# Trainiiii_Cape.net
KiCad netlist of a schematic drawn in EAGLE
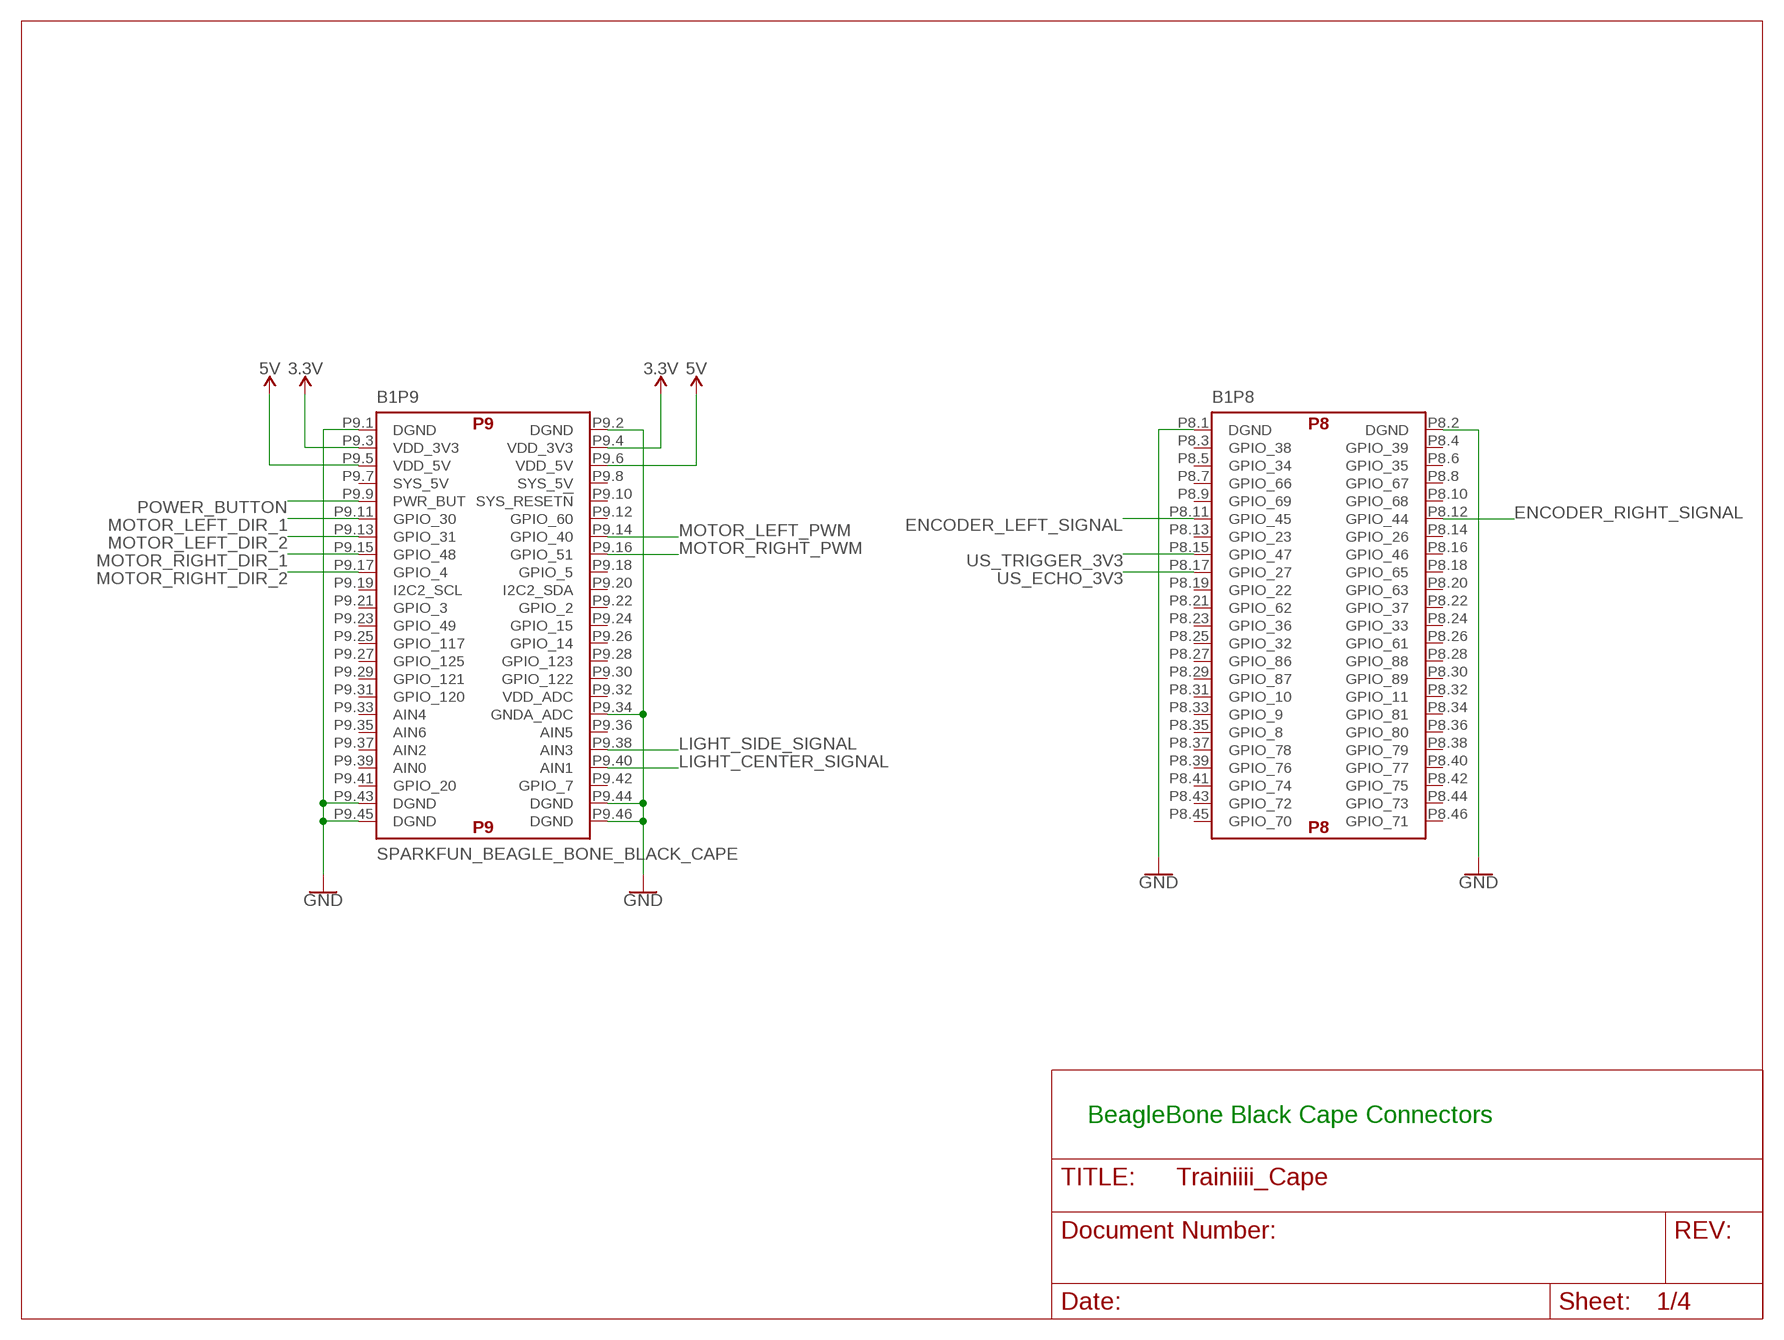
[diagram p0: schematic, sheet 1]
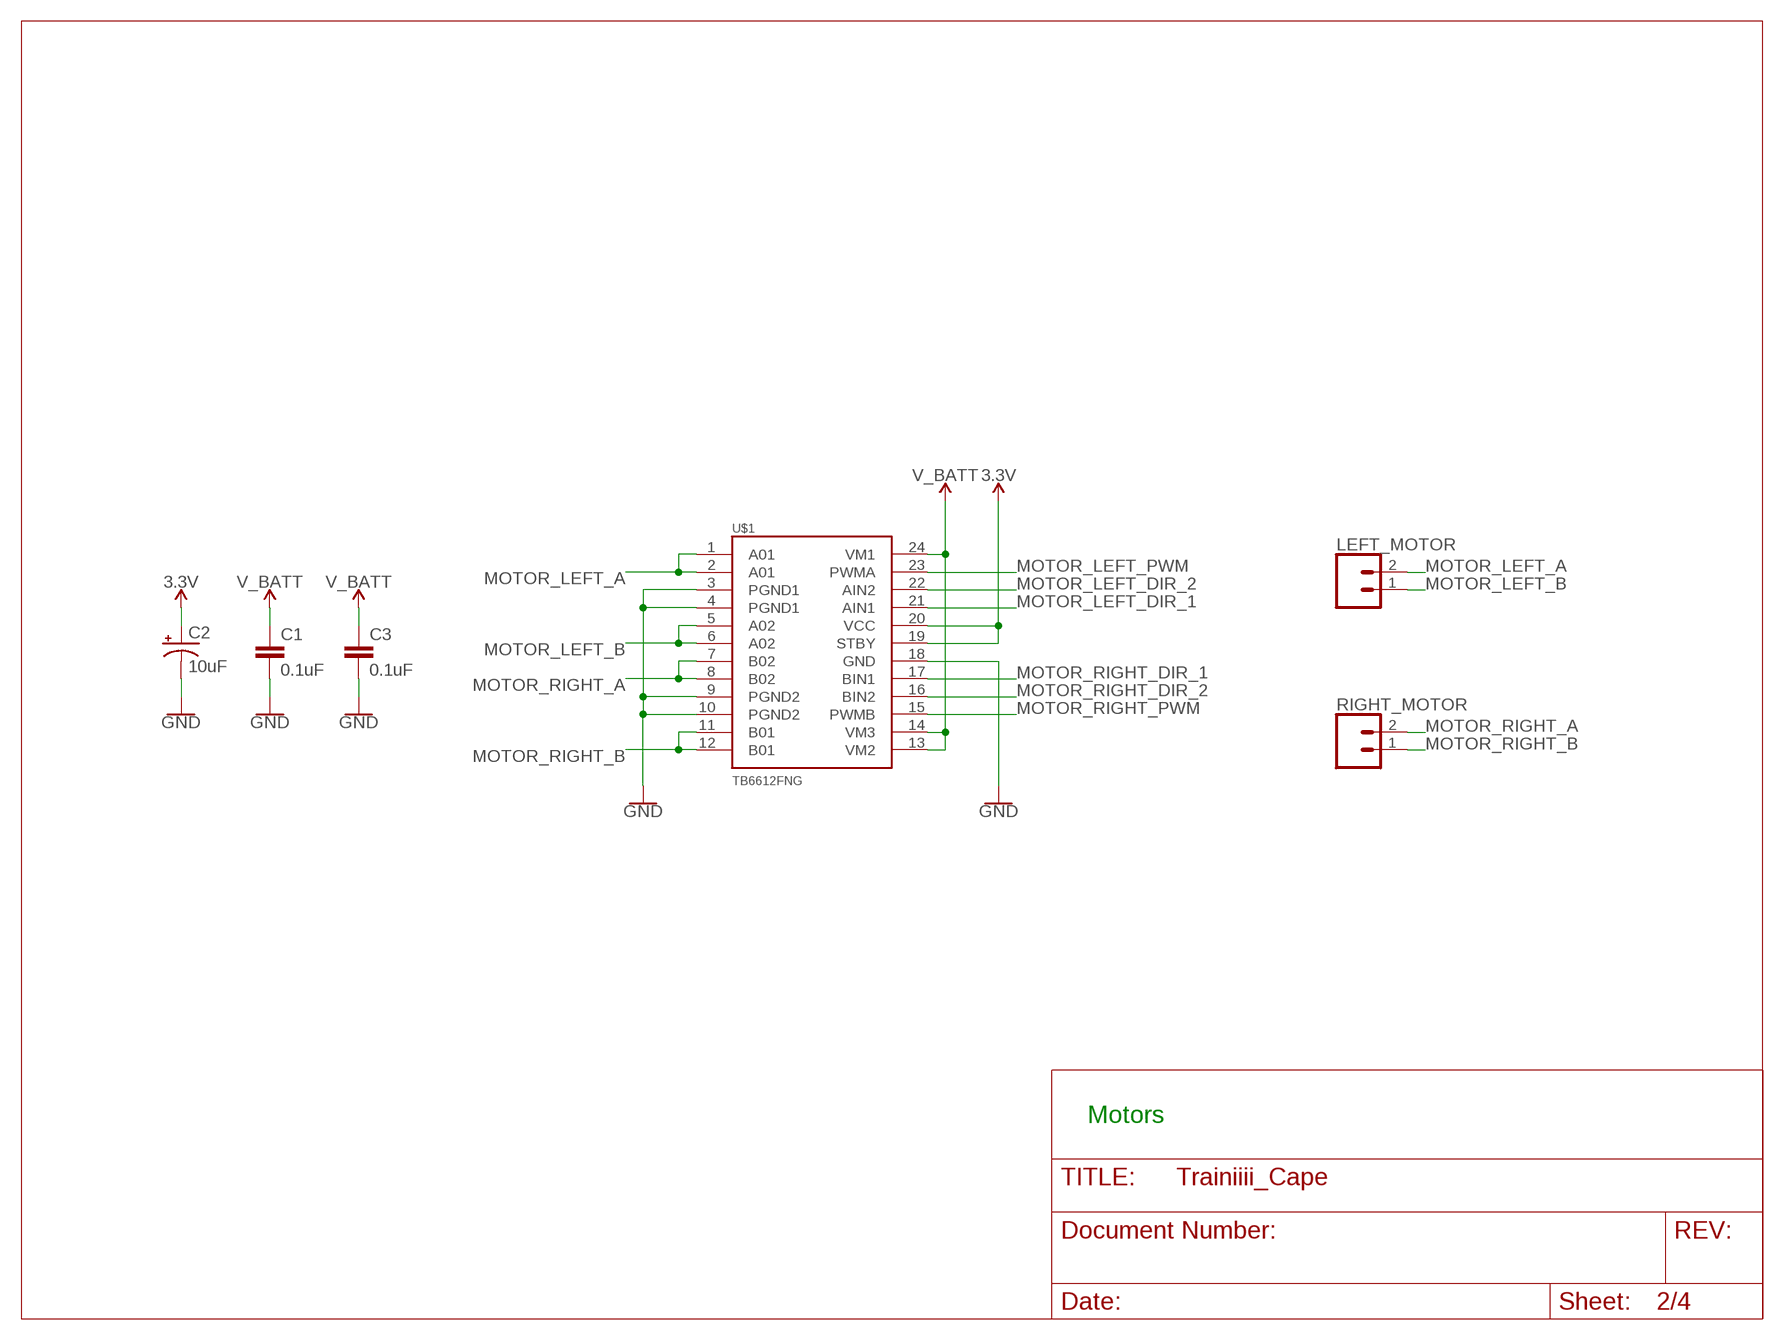
[diagram p1: schematic, sheet 2]
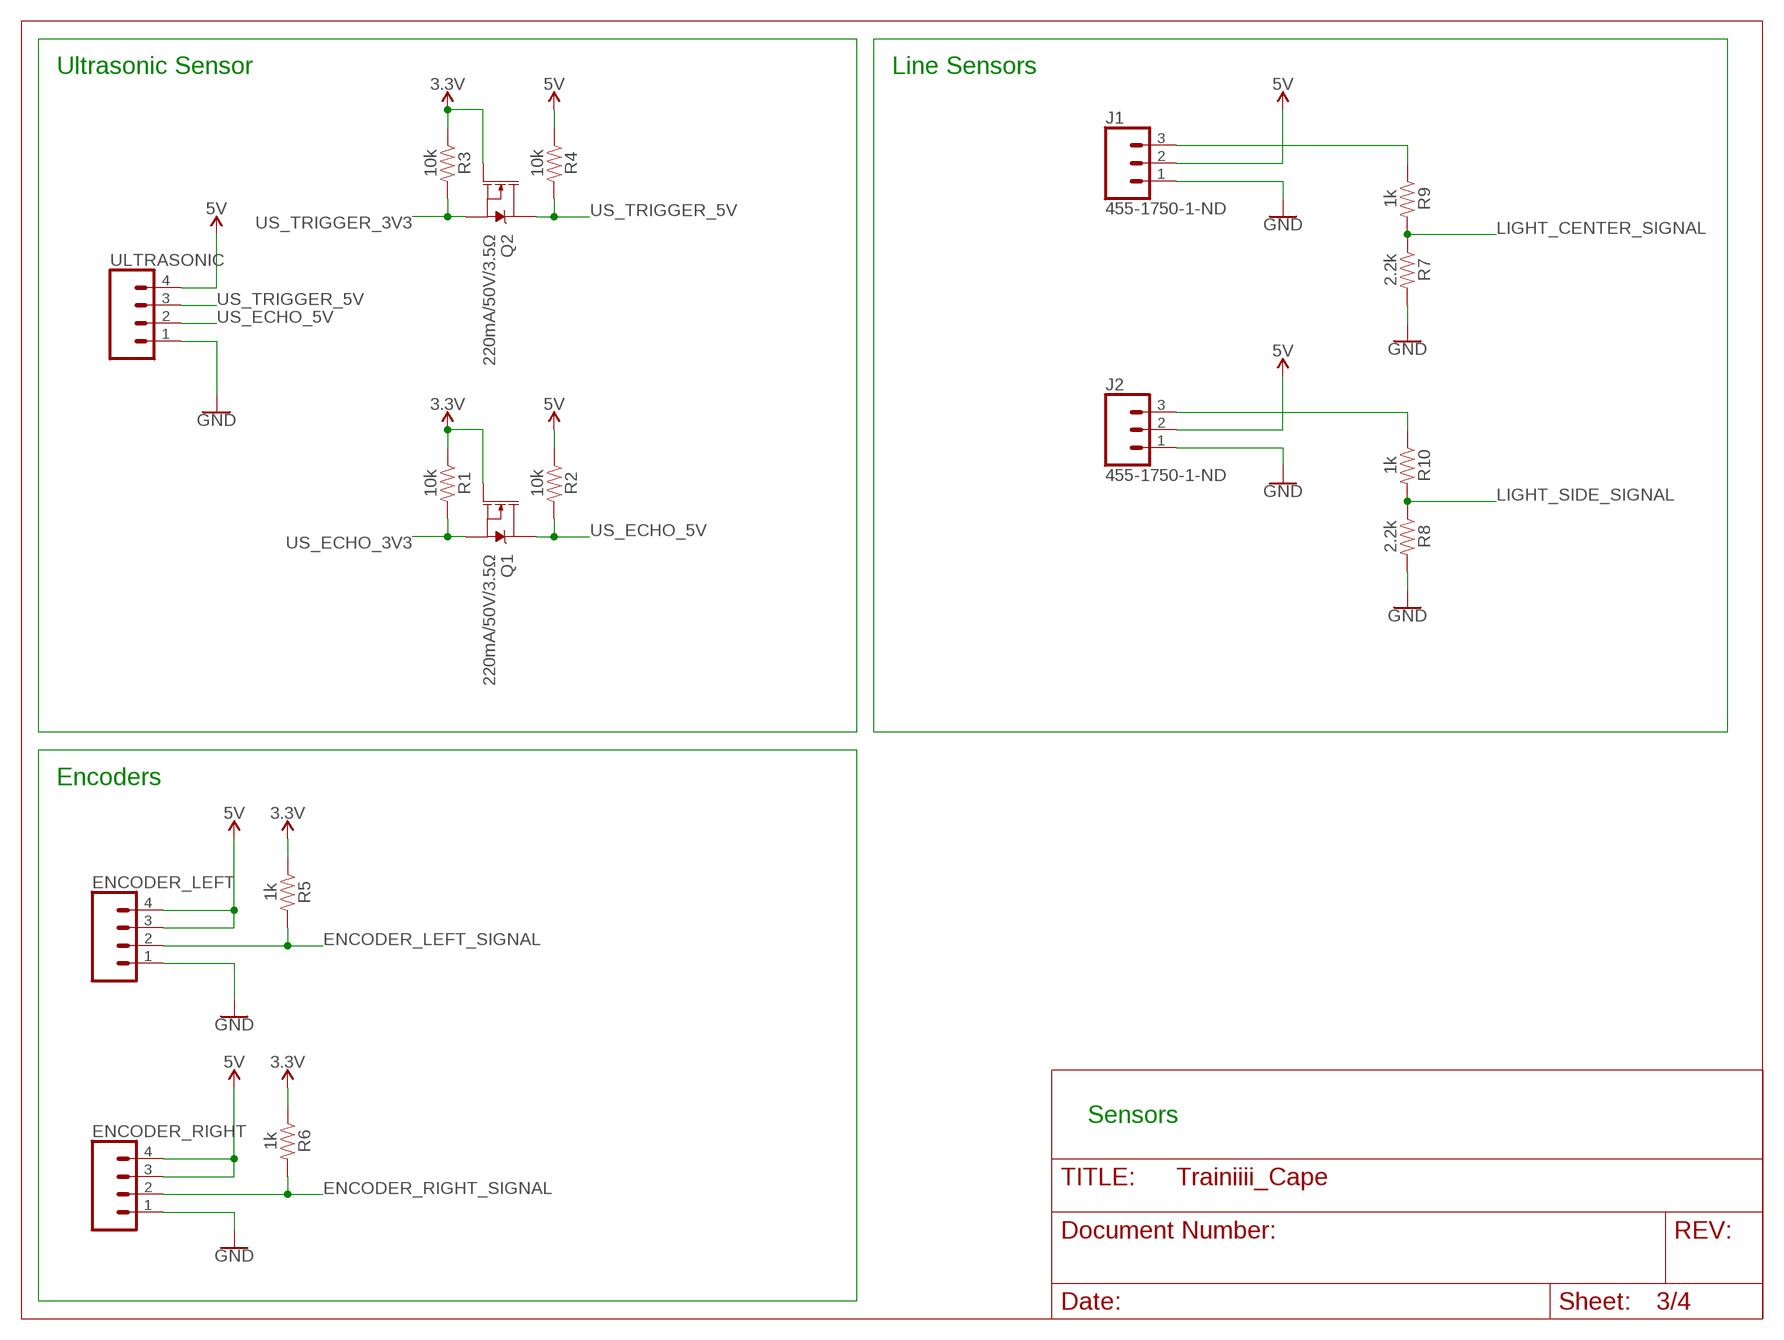
[diagram p2: schematic, sheet 3]
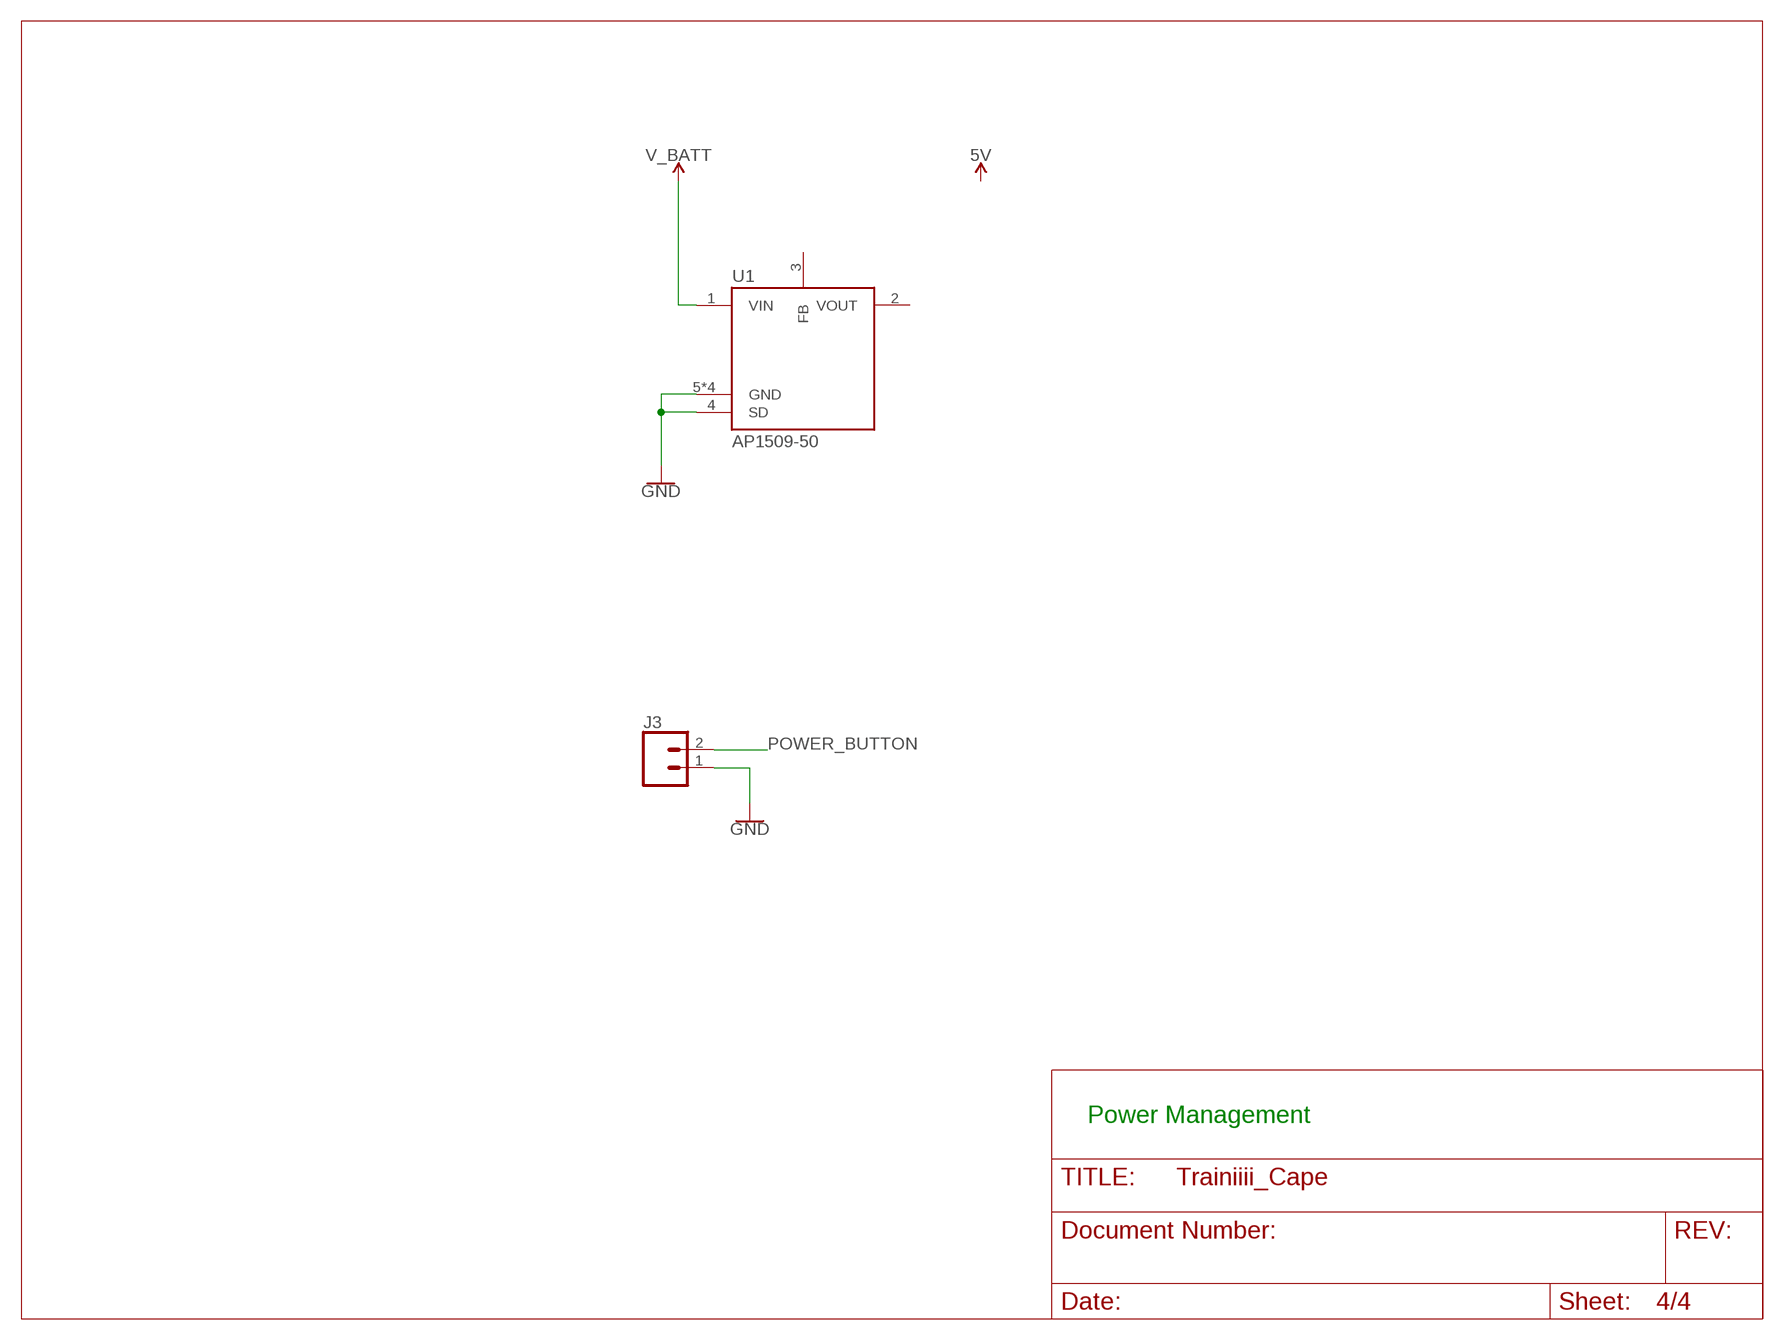
[diagram p3: schematic, sheet 4]

(export (version "E")
  (design (tool "Eeschema 10.0.6"))
  (components
    (comp (ref "ENCODER_LEFT")
      (value "CONN_04PTH")
      (footprint "eagle-import:1X04")
      (libsource (lib "eagle-import") (part "CONN_04PTH"))
    )
    (comp (ref "ENCODER_RIGHT")
      (value "CONN_04PTH")
      (footprint "eagle-import:1X04")
      (libsource (lib "eagle-import") (part "CONN_04PTH"))
    )
    (comp (ref "J1")
      (value "455-1750-1-ND")
      (footprint "eagle-import:1X03")
      (libsource (lib "eagle-import") (part "CONN_03"))
    )
    (comp (ref "J2")
      (value "455-1750-1-ND")
      (footprint "eagle-import:1X03")
      (libsource (lib "eagle-import") (part "CONN_03"))
    )
    (comp (ref "Q1")
      (value "220mA/50V/3.5Ω")
      (footprint "eagle-import:SOT23-3")
      (libsource (lib "eagle-import") (part "MOSFET-NCH-BSS138"))
    )
    (comp (ref "Q2")
      (value "220mA/50V/3.5Ω")
      (footprint "eagle-import:SOT23-3")
      (libsource (lib "eagle-import") (part "MOSFET-NCH-BSS138"))
    )
    (comp (ref "R1")
      (value "10k")
      (footprint "eagle-import:0603")
      (libsource (lib "eagle-import") (part "10KOHM-0603-1/10W-1%"))
    )
    (comp (ref "R2")
      (value "10k")
      (footprint "eagle-import:0603")
      (libsource (lib "eagle-import") (part "10KOHM-0603-1/10W-1%"))
    )
    (comp (ref "R3")
      (value "10k")
      (footprint "eagle-import:0603")
      (libsource (lib "eagle-import") (part "10KOHM-0603-1/10W-1%"))
    )
    (comp (ref "R4")
      (value "10k")
      (footprint "eagle-import:0603")
      (libsource (lib "eagle-import") (part "10KOHM-0603-1/10W-1%"))
    )
    (comp (ref "R5")
      (value "1k")
      (footprint "eagle-import:0603")
      (libsource (lib "eagle-import") (part "1KOHM-0603-1/10W-1%"))
    )
    (comp (ref "R6")
      (value "1k")
      (footprint "eagle-import:0603")
      (libsource (lib "eagle-import") (part "1KOHM-0603-1/10W-1%"))
    )
    (comp (ref "R7")
      (value "2.2k")
      (footprint "eagle-import:0603")
      (libsource (lib "eagle-import") (part "2.2KOHM-0603-1/10W-1%"))
    )
    (comp (ref "R8")
      (value "2.2k")
      (footprint "eagle-import:0603")
      (libsource (lib "eagle-import") (part "2.2KOHM-0603-1/10W-1%"))
    )
    (comp (ref "R9")
      (value "1k")
      (footprint "eagle-import:0603")
      (libsource (lib "eagle-import") (part "1KOHM-0603-1/10W-1%"))
    )
    (comp (ref "R10")
      (value "1k")
      (footprint "eagle-import:0603")
      (libsource (lib "eagle-import") (part "1KOHM-0603-1/10W-1%"))
    )
    (comp (ref "ULTRASONIC")
      (value "CONN_04PTH")
      (footprint "eagle-import:1X04")
      (libsource (lib "eagle-import") (part "CONN_04PTH"))
    )
    (comp (ref "C1")
      (value "0.1uF")
      (footprint "eagle-import:0402")
      (libsource (lib "eagle-import") (part "0.1UF-0402-16V-10%"))
    )
    (comp (ref "C2")
      (value "10uF")
      (footprint "eagle-import:EIA3528")
      (libsource (lib "eagle-import") (part "10UF-POLAR-EIA3528-20V-10%(TANT)"))
    )
    (comp (ref "C3")
      (value "0.1uF")
      (footprint "eagle-import:0402")
      (libsource (lib "eagle-import") (part "0.1UF-0402-16V-10%"))
    )
    (comp (ref "LEFT_MOTOR")
      (value "CONN_02")
      (footprint "eagle-import:1X02")
      (libsource (lib "eagle-import") (part "CONN_02"))
    )
    (comp (ref "RIGHT_MOTOR")
      (value "CONN_02")
      (footprint "eagle-import:1X02")
      (libsource (lib "eagle-import") (part "CONN_02"))
    )
    (comp (ref "U$1")
      (value "TB6612FNG")
      (footprint "eagle-import:SSOP24")
      (libsource (lib "eagle-import") (part "TB6612FNG"))
    )
    (comp (ref "J3")
      (value "CONN_02")
      (footprint "eagle-import:1X02")
      (libsource (lib "eagle-import") (part "CONN_02"))
    )
    (comp (ref "U1")
      (value "AP1509-50")
      (footprint "eagle-import:SOIC-8")
      (libsource (lib "eagle-import") (part "AP1509-50"))
    )
    (comp (ref "B1")
      (value "SPARKFUN_BEAGLE_BONE_BLACK_CAPE")
      (footprint "eagle-import:BEAGLE_BONE_BLACK_CAPE")
      (libsource (lib "eagle-import") (part "SPARKFUN_BEAGLE_BONE_BLACK_CAPE"))
    )
  )
  (nets
    (net (code "1") (name "3.3V") (class "Default")
      (node (ref "B1") (pin "P9.3") (pinfunction "VDD_3V3_P9.3") (pintype "bidirectional"))
      (node (ref "B1") (pin "P9.4") (pinfunction "VDD_3V3_P9.4") (pintype "bidirectional"))
      (node (ref "C2") (pin "A") (pinfunction "+_A") (pintype "passive"))
      (node (ref "Q1") (pin "1") (pinfunction "G_1") (pintype "bidirectional"))
      (node (ref "Q2") (pin "1") (pinfunction "G_1") (pintype "bidirectional"))
      (node (ref "R1") (pin "1") (pinfunction "1_1") (pintype "passive"))
      (node (ref "R3") (pin "1") (pinfunction "1_1") (pintype "passive"))
      (node (ref "R5") (pin "1") (pinfunction "1_1") (pintype "passive"))
      (node (ref "R6") (pin "1") (pinfunction "1_1") (pintype "passive"))
      (node (ref "U$1") (pin "19") (pinfunction "STBY_19") (pintype "bidirectional"))
      (node (ref "U$1") (pin "20") (pinfunction "VCC_20") (pintype "bidirectional"))
    )
    (net (code "2") (name "5V") (class "Default")
      (node (ref "B1") (pin "P9.5") (pinfunction "VDD_5V_P9.5") (pintype "bidirectional"))
      (node (ref "B1") (pin "P9.6") (pinfunction "VDD_5V_P9.6") (pintype "bidirectional"))
      (node (ref "ENCODER_LEFT") (pin "3") (pinfunction "3_3") (pintype "passive"))
      (node (ref "ENCODER_LEFT") (pin "4") (pinfunction "4_4") (pintype "passive"))
      (node (ref "ENCODER_RIGHT") (pin "3") (pinfunction "3_3") (pintype "passive"))
      (node (ref "ENCODER_RIGHT") (pin "4") (pinfunction "4_4") (pintype "passive"))
      (node (ref "J1") (pin "2") (pinfunction "2_2") (pintype "passive"))
      (node (ref "J2") (pin "2") (pinfunction "2_2") (pintype "passive"))
      (node (ref "R2") (pin "1") (pinfunction "1_1") (pintype "passive"))
      (node (ref "R4") (pin "1") (pinfunction "1_1") (pintype "passive"))
      (node (ref "ULTRASONIC") (pin "4") (pinfunction "4_4") (pintype "passive"))
    )
    (net (code "3") (name "ENCODER_LEFT_SIGNAL") (class "Default")
      (node (ref "B1") (pin "P8.11") (pinfunction "GPIO_45_P8.11") (pintype "bidirectional"))
      (node (ref "ENCODER_LEFT") (pin "2") (pinfunction "2_2") (pintype "passive"))
      (node (ref "R5") (pin "2") (pinfunction "2_2") (pintype "passive"))
    )
    (net (code "4") (name "ENCODER_RIGHT_SIGNAL") (class "Default")
      (node (ref "B1") (pin "P8.12") (pinfunction "GPIO_44_P8.12") (pintype "bidirectional"))
      (node (ref "ENCODER_RIGHT") (pin "2") (pinfunction "2_2") (pintype "passive"))
      (node (ref "R6") (pin "2") (pinfunction "2_2") (pintype "passive"))
    )
    (net (code "5") (name "GND") (class "Default")
      (node (ref "B1") (pin "P8.1") (pinfunction "DGND_P8.1") (pintype "bidirectional"))
      (node (ref "B1") (pin "P8.2") (pinfunction "DGND_P8.2") (pintype "bidirectional"))
      (node (ref "B1") (pin "P9.1") (pinfunction "DGND_P9.1") (pintype "bidirectional"))
      (node (ref "B1") (pin "P9.2") (pinfunction "DGND_P9.2") (pintype "bidirectional"))
      (node (ref "B1") (pin "P9.34") (pinfunction "GNDA_ADC_P9.34") (pintype "bidirectional"))
      (node (ref "B1") (pin "P9.43") (pinfunction "DGND_P9.43") (pintype "bidirectional"))
      (node (ref "B1") (pin "P9.44") (pinfunction "DGND_P9.44") (pintype "bidirectional"))
      (node (ref "B1") (pin "P9.45") (pinfunction "DGND_P9.45") (pintype "bidirectional"))
      (node (ref "B1") (pin "P9.46") (pinfunction "DGND_P9.46") (pintype "bidirectional"))
      (node (ref "C1") (pin "2") (pinfunction "2_2") (pintype "passive"))
      (node (ref "C2") (pin "C") (pinfunction "-_C") (pintype "passive"))
      (node (ref "C3") (pin "2") (pinfunction "2_2") (pintype "passive"))
      (node (ref "ENCODER_LEFT") (pin "1") (pinfunction "1_1") (pintype "passive"))
      (node (ref "ENCODER_RIGHT") (pin "1") (pinfunction "1_1") (pintype "passive"))
      (node (ref "J1") (pin "1") (pinfunction "1_1") (pintype "passive"))
      (node (ref "J2") (pin "1") (pinfunction "1_1") (pintype "passive"))
      (node (ref "J3") (pin "1") (pinfunction "1_1") (pintype "passive"))
      (node (ref "R7") (pin "2") (pinfunction "2_2") (pintype "passive"))
      (node (ref "R8") (pin "2") (pinfunction "2_2") (pintype "passive"))
      (node (ref "U$1") (pin "10") (pinfunction "PGND2_10") (pintype "bidirectional"))
      (node (ref "U$1") (pin "18") (pinfunction "GND_18") (pintype "bidirectional"))
      (node (ref "U$1") (pin "3") (pinfunction "PGND1_3") (pintype "bidirectional"))
      (node (ref "U$1") (pin "4") (pinfunction "PGND1_4") (pintype "bidirectional"))
      (node (ref "U$1") (pin "9") (pinfunction "PGND2_9") (pintype "bidirectional"))
      (node (ref "U1") (pin "4") (pinfunction "SD_4") (pintype "bidirectional"))
      (node (ref "U1") (pin "5") (pinfunction "GND_5") (pintype "bidirectional"))
      (node (ref "U1") (pin "6") (pinfunction "GND_6") (pintype "bidirectional"))
      (node (ref "U1") (pin "7") (pinfunction "GND_7") (pintype "bidirectional"))
      (node (ref "U1") (pin "8") (pinfunction "GND_8") (pintype "bidirectional"))
      (node (ref "ULTRASONIC") (pin "1") (pinfunction "1_1") (pintype "passive"))
    )
    (net (code "6") (name "LIGHT_CENTER_SIGNAL") (class "Default")
      (node (ref "B1") (pin "P9.40") (pinfunction "AIN1_P9.40") (pintype "bidirectional"))
      (node (ref "R7") (pin "1") (pinfunction "1_1") (pintype "passive"))
      (node (ref "R9") (pin "2") (pinfunction "2_2") (pintype "passive"))
    )
    (net (code "7") (name "LIGHT_SIDE_SIGNAL") (class "Default")
      (node (ref "B1") (pin "P9.38") (pinfunction "AIN3_P9.38") (pintype "bidirectional"))
      (node (ref "R10") (pin "2") (pinfunction "2_2") (pintype "passive"))
      (node (ref "R8") (pin "1") (pinfunction "1_1") (pintype "passive"))
    )
    (net (code "8") (name "MOTOR_LEFT_A") (class "Default")
      (node (ref "LEFT_MOTOR") (pin "2") (pinfunction "2_2") (pintype "passive"))
      (node (ref "U$1") (pin "1") (pinfunction "A01_1") (pintype "bidirectional"))
      (node (ref "U$1") (pin "2") (pinfunction "A01_2") (pintype "bidirectional"))
    )
    (net (code "9") (name "MOTOR_LEFT_B") (class "Default")
      (node (ref "LEFT_MOTOR") (pin "1") (pinfunction "1_1") (pintype "passive"))
      (node (ref "U$1") (pin "5") (pinfunction "A02_5") (pintype "bidirectional"))
      (node (ref "U$1") (pin "6") (pinfunction "A02_6") (pintype "bidirectional"))
    )
    (net (code "10") (name "MOTOR_LEFT_DIR_1") (class "Default")
      (node (ref "B1") (pin "P9.11") (pinfunction "GPIO_30_P9.11") (pintype "bidirectional"))
      (node (ref "U$1") (pin "21") (pinfunction "AIN1_21") (pintype "bidirectional"))
    )
    (net (code "11") (name "MOTOR_LEFT_DIR_2") (class "Default")
      (node (ref "B1") (pin "P9.13") (pinfunction "GPIO_31_P9.13") (pintype "bidirectional"))
      (node (ref "U$1") (pin "22") (pinfunction "AIN2_22") (pintype "bidirectional"))
    )
    (net (code "12") (name "MOTOR_LEFT_PWM") (class "Default")
      (node (ref "B1") (pin "P9.14") (pinfunction "GPIO_40_P9.14") (pintype "bidirectional"))
      (node (ref "U$1") (pin "23") (pinfunction "PWMA_23") (pintype "bidirectional"))
    )
    (net (code "13") (name "MOTOR_RIGHT_A") (class "Default")
      (node (ref "RIGHT_MOTOR") (pin "2") (pinfunction "2_2") (pintype "passive"))
      (node (ref "U$1") (pin "7") (pinfunction "B02_7") (pintype "bidirectional"))
      (node (ref "U$1") (pin "8") (pinfunction "B02_8") (pintype "bidirectional"))
    )
    (net (code "14") (name "MOTOR_RIGHT_B") (class "Default")
      (node (ref "RIGHT_MOTOR") (pin "1") (pinfunction "1_1") (pintype "passive"))
      (node (ref "U$1") (pin "11") (pinfunction "B01_11") (pintype "bidirectional"))
      (node (ref "U$1") (pin "12") (pinfunction "B01_12") (pintype "bidirectional"))
    )
    (net (code "15") (name "MOTOR_RIGHT_DIR_1") (class "Default")
      (node (ref "B1") (pin "P9.15") (pinfunction "GPIO_48_P9.15") (pintype "bidirectional"))
      (node (ref "U$1") (pin "17") (pinfunction "BIN1_17") (pintype "bidirectional"))
    )
    (net (code "16") (name "MOTOR_RIGHT_DIR_2") (class "Default")
      (node (ref "B1") (pin "P9.17") (pinfunction "GPIO_4_P9.17") (pintype "bidirectional"))
      (node (ref "U$1") (pin "16") (pinfunction "BIN2_16") (pintype "bidirectional"))
    )
    (net (code "17") (name "MOTOR_RIGHT_PWM") (class "Default")
      (node (ref "B1") (pin "P9.16") (pinfunction "GPIO_51_P9.16") (pintype "bidirectional"))
      (node (ref "U$1") (pin "15") (pinfunction "PWMB_15") (pintype "bidirectional"))
    )
    (net (code "18") (name "Net-(J1-Pad3)") (class "Default")
      (node (ref "J1") (pin "3") (pinfunction "3_3") (pintype "passive"))
      (node (ref "R9") (pin "1") (pinfunction "1_1") (pintype "passive"))
    )
    (net (code "19") (name "Net-(J2-Pad3)") (class "Default")
      (node (ref "J2") (pin "3") (pinfunction "3_3") (pintype "passive"))
      (node (ref "R10") (pin "1") (pinfunction "1_1") (pintype "passive"))
    )
    (net (code "20") (name "POWER_BUTTON") (class "Default")
      (node (ref "B1") (pin "P9.9") (pinfunction "PWR_BUT_P9.9") (pintype "bidirectional"))
      (node (ref "J3") (pin "2") (pinfunction "2_2") (pintype "passive"))
    )
    (net (code "21") (name "US_ECHO_3V3") (class "Default")
      (node (ref "B1") (pin "P8.17") (pinfunction "GPIO_27_P8.17") (pintype "bidirectional"))
      (node (ref "Q1") (pin "2") (pinfunction "S_2") (pintype "bidirectional"))
      (node (ref "R1") (pin "2") (pinfunction "2_2") (pintype "passive"))
    )
    (net (code "22") (name "US_ECHO_5V") (class "Default")
      (node (ref "Q1") (pin "3") (pinfunction "D_3") (pintype "bidirectional"))
      (node (ref "R2") (pin "2") (pinfunction "2_2") (pintype "passive"))
      (node (ref "ULTRASONIC") (pin "2") (pinfunction "2_2") (pintype "passive"))
    )
    (net (code "23") (name "US_TRIGGER_3V3") (class "Default")
      (node (ref "B1") (pin "P8.15") (pinfunction "GPIO_47_P8.15") (pintype "bidirectional"))
      (node (ref "Q2") (pin "2") (pinfunction "S_2") (pintype "bidirectional"))
      (node (ref "R3") (pin "2") (pinfunction "2_2") (pintype "passive"))
    )
    (net (code "24") (name "US_TRIGGER_5V") (class "Default")
      (node (ref "Q2") (pin "3") (pinfunction "D_3") (pintype "bidirectional"))
      (node (ref "R4") (pin "2") (pinfunction "2_2") (pintype "passive"))
      (node (ref "ULTRASONIC") (pin "3") (pinfunction "3_3") (pintype "passive"))
    )
    (net (code "25") (name "V_BATT") (class "Default")
      (node (ref "C1") (pin "1") (pinfunction "1_1") (pintype "passive"))
      (node (ref "C3") (pin "1") (pinfunction "1_1") (pintype "passive"))
      (node (ref "U$1") (pin "13") (pinfunction "VM2_13") (pintype "bidirectional"))
      (node (ref "U$1") (pin "14") (pinfunction "VM3_14") (pintype "bidirectional"))
      (node (ref "U$1") (pin "24") (pinfunction "VM1_24") (pintype "bidirectional"))
      (node (ref "U1") (pin "1") (pinfunction "VIN_1") (pintype "bidirectional"))
    )
    (net (code "26") (name "unconnected-(B1A-GPIO_8-PadP8.35)") (class "Default")
      (node (ref "B1") (pin "P8.35") (pinfunction "GPIO_8_P8.35") (pintype "bidirectional"))
    )
    (net (code "27") (name "unconnected-(B1A-GPIO_9-PadP8.33)") (class "Default")
      (node (ref "B1") (pin "P8.33") (pinfunction "GPIO_9_P8.33") (pintype "bidirectional"))
    )
    (net (code "28") (name "unconnected-(B1A-GPIO_10-PadP8.31)") (class "Default")
      (node (ref "B1") (pin "P8.31") (pinfunction "GPIO_10_P8.31") (pintype "bidirectional"))
    )
    (net (code "29") (name "unconnected-(B1A-GPIO_11-PadP8.32)") (class "Default")
      (node (ref "B1") (pin "P8.32") (pinfunction "GPIO_11_P8.32") (pintype "bidirectional"))
    )
    (net (code "30") (name "unconnected-(B1A-GPIO_22-PadP8.19)") (class "Default")
      (node (ref "B1") (pin "P8.19") (pinfunction "GPIO_22_P8.19") (pintype "bidirectional"))
    )
    (net (code "31") (name "unconnected-(B1A-GPIO_23-PadP8.13)") (class "Default")
      (node (ref "B1") (pin "P8.13") (pinfunction "GPIO_23_P8.13") (pintype "bidirectional"))
    )
    (net (code "32") (name "unconnected-(B1A-GPIO_26-PadP8.14)") (class "Default")
      (node (ref "B1") (pin "P8.14") (pinfunction "GPIO_26_P8.14") (pintype "bidirectional"))
    )
    (net (code "33") (name "unconnected-(B1A-GPIO_32-PadP8.25)") (class "Default")
      (node (ref "B1") (pin "P8.25") (pinfunction "GPIO_32_P8.25") (pintype "bidirectional"))
    )
    (net (code "34") (name "unconnected-(B1A-GPIO_33-PadP8.24)") (class "Default")
      (node (ref "B1") (pin "P8.24") (pinfunction "GPIO_33_P8.24") (pintype "bidirectional"))
    )
    (net (code "35") (name "unconnected-(B1A-GPIO_34-PadP8.5)") (class "Default")
      (node (ref "B1") (pin "P8.5") (pinfunction "GPIO_34_P8.5") (pintype "bidirectional"))
    )
    (net (code "36") (name "unconnected-(B1A-GPIO_35-PadP8.6)") (class "Default")
      (node (ref "B1") (pin "P8.6") (pinfunction "GPIO_35_P8.6") (pintype "bidirectional"))
    )
    (net (code "37") (name "unconnected-(B1A-GPIO_36-PadP8.23)") (class "Default")
      (node (ref "B1") (pin "P8.23") (pinfunction "GPIO_36_P8.23") (pintype "bidirectional"))
    )
    (net (code "38") (name "unconnected-(B1A-GPIO_37-PadP8.22)") (class "Default")
      (node (ref "B1") (pin "P8.22") (pinfunction "GPIO_37_P8.22") (pintype "bidirectional"))
    )
    (net (code "39") (name "unconnected-(B1A-GPIO_38-PadP8.3)") (class "Default")
      (node (ref "B1") (pin "P8.3") (pinfunction "GPIO_38_P8.3") (pintype "bidirectional"))
    )
    (net (code "40") (name "unconnected-(B1A-GPIO_39-PadP8.4)") (class "Default")
      (node (ref "B1") (pin "P8.4") (pinfunction "GPIO_39_P8.4") (pintype "bidirectional"))
    )
    (net (code "41") (name "unconnected-(B1A-GPIO_46-PadP8.16)") (class "Default")
      (node (ref "B1") (pin "P8.16") (pinfunction "GPIO_46_P8.16") (pintype "bidirectional"))
    )
    (net (code "42") (name "unconnected-(B1A-GPIO_61-PadP8.26)") (class "Default")
      (node (ref "B1") (pin "P8.26") (pinfunction "GPIO_61_P8.26") (pintype "bidirectional"))
    )
    (net (code "43") (name "unconnected-(B1A-GPIO_62-PadP8.21)") (class "Default")
      (node (ref "B1") (pin "P8.21") (pinfunction "GPIO_62_P8.21") (pintype "bidirectional"))
    )
    (net (code "44") (name "unconnected-(B1A-GPIO_63-PadP8.20)") (class "Default")
      (node (ref "B1") (pin "P8.20") (pinfunction "GPIO_63_P8.20") (pintype "bidirectional"))
    )
    (net (code "45") (name "unconnected-(B1A-GPIO_65-PadP8.18)") (class "Default")
      (node (ref "B1") (pin "P8.18") (pinfunction "GPIO_65_P8.18") (pintype "bidirectional"))
    )
    (net (code "46") (name "unconnected-(B1A-GPIO_66-PadP8.7)") (class "Default")
      (node (ref "B1") (pin "P8.7") (pinfunction "GPIO_66_P8.7") (pintype "bidirectional"))
    )
    (net (code "47") (name "unconnected-(B1A-GPIO_67-PadP8.8)") (class "Default")
      (node (ref "B1") (pin "P8.8") (pinfunction "GPIO_67_P8.8") (pintype "bidirectional"))
    )
    (net (code "48") (name "unconnected-(B1A-GPIO_68-PadP8.10)") (class "Default")
      (node (ref "B1") (pin "P8.10") (pinfunction "GPIO_68_P8.10") (pintype "bidirectional"))
    )
    (net (code "49") (name "unconnected-(B1A-GPIO_69-PadP8.9)") (class "Default")
      (node (ref "B1") (pin "P8.9") (pinfunction "GPIO_69_P8.9") (pintype "bidirectional"))
    )
    (net (code "50") (name "unconnected-(B1A-GPIO_70-PadP8.45)") (class "Default")
      (node (ref "B1") (pin "P8.45") (pinfunction "GPIO_70_P8.45") (pintype "bidirectional"))
    )
    (net (code "51") (name "unconnected-(B1A-GPIO_71-PadP8.46)") (class "Default")
      (node (ref "B1") (pin "P8.46") (pinfunction "GPIO_71_P8.46") (pintype "bidirectional"))
    )
    (net (code "52") (name "unconnected-(B1A-GPIO_72-PadP8.43)") (class "Default")
      (node (ref "B1") (pin "P8.43") (pinfunction "GPIO_72_P8.43") (pintype "bidirectional"))
    )
    (net (code "53") (name "unconnected-(B1A-GPIO_73-PadP8.44)") (class "Default")
      (node (ref "B1") (pin "P8.44") (pinfunction "GPIO_73_P8.44") (pintype "bidirectional"))
    )
    (net (code "54") (name "unconnected-(B1A-GPIO_74-PadP8.41)") (class "Default")
      (node (ref "B1") (pin "P8.41") (pinfunction "GPIO_74_P8.41") (pintype "bidirectional"))
    )
    (net (code "55") (name "unconnected-(B1A-GPIO_75-PadP8.42)") (class "Default")
      (node (ref "B1") (pin "P8.42") (pinfunction "GPIO_75_P8.42") (pintype "bidirectional"))
    )
    (net (code "56") (name "unconnected-(B1A-GPIO_76-PadP8.39)") (class "Default")
      (node (ref "B1") (pin "P8.39") (pinfunction "GPIO_76_P8.39") (pintype "bidirectional"))
    )
    (net (code "57") (name "unconnected-(B1A-GPIO_77-PadP8.40)") (class "Default")
      (node (ref "B1") (pin "P8.40") (pinfunction "GPIO_77_P8.40") (pintype "bidirectional"))
    )
    (net (code "58") (name "unconnected-(B1A-GPIO_78-PadP8.37)") (class "Default")
      (node (ref "B1") (pin "P8.37") (pinfunction "GPIO_78_P8.37") (pintype "bidirectional"))
    )
    (net (code "59") (name "unconnected-(B1A-GPIO_79-PadP8.38)") (class "Default")
      (node (ref "B1") (pin "P8.38") (pinfunction "GPIO_79_P8.38") (pintype "bidirectional"))
    )
    (net (code "60") (name "unconnected-(B1A-GPIO_80-PadP8.36)") (class "Default")
      (node (ref "B1") (pin "P8.36") (pinfunction "GPIO_80_P8.36") (pintype "bidirectional"))
    )
    (net (code "61") (name "unconnected-(B1A-GPIO_81-PadP8.34)") (class "Default")
      (node (ref "B1") (pin "P8.34") (pinfunction "GPIO_81_P8.34") (pintype "bidirectional"))
    )
    (net (code "62") (name "unconnected-(B1A-GPIO_86-PadP8.27)") (class "Default")
      (node (ref "B1") (pin "P8.27") (pinfunction "GPIO_86_P8.27") (pintype "bidirectional"))
    )
    (net (code "63") (name "unconnected-(B1A-GPIO_87-PadP8.29)") (class "Default")
      (node (ref "B1") (pin "P8.29") (pinfunction "GPIO_87_P8.29") (pintype "bidirectional"))
    )
    (net (code "64") (name "unconnected-(B1A-GPIO_88-PadP8.28)") (class "Default")
      (node (ref "B1") (pin "P8.28") (pinfunction "GPIO_88_P8.28") (pintype "bidirectional"))
    )
    (net (code "65") (name "unconnected-(B1A-GPIO_89-PadP8.30)") (class "Default")
      (node (ref "B1") (pin "P8.30") (pinfunction "GPIO_89_P8.30") (pintype "bidirectional"))
    )
    (net (code "66") (name "unconnected-(B1B-AIN0-PadP9.39)") (class "Default")
      (node (ref "B1") (pin "P9.39") (pinfunction "AIN0_P9.39") (pintype "bidirectional"))
    )
    (net (code "67") (name "unconnected-(B1B-AIN2-PadP9.37)") (class "Default")
      (node (ref "B1") (pin "P9.37") (pinfunction "AIN2_P9.37") (pintype "bidirectional"))
    )
    (net (code "68") (name "unconnected-(B1B-AIN4-PadP9.33)") (class "Default")
      (node (ref "B1") (pin "P9.33") (pinfunction "AIN4_P9.33") (pintype "bidirectional"))
    )
    (net (code "69") (name "unconnected-(B1B-AIN5-PadP9.36)") (class "Default")
      (node (ref "B1") (pin "P9.36") (pinfunction "AIN5_P9.36") (pintype "bidirectional"))
    )
    (net (code "70") (name "unconnected-(B1B-AIN6-PadP9.35)") (class "Default")
      (node (ref "B1") (pin "P9.35") (pinfunction "AIN6_P9.35") (pintype "bidirectional"))
    )
    (net (code "71") (name "unconnected-(B1B-GPIO_2-PadP9.22)") (class "Default")
      (node (ref "B1") (pin "P9.22") (pinfunction "GPIO_2_P9.22") (pintype "bidirectional"))
    )
    (net (code "72") (name "unconnected-(B1B-GPIO_3-PadP9.21)") (class "Default")
      (node (ref "B1") (pin "P9.21") (pinfunction "GPIO_3_P9.21") (pintype "bidirectional"))
    )
    (net (code "73") (name "unconnected-(B1B-GPIO_5-PadP9.18)") (class "Default")
      (node (ref "B1") (pin "P9.18") (pinfunction "GPIO_5_P9.18") (pintype "bidirectional"))
    )
    (net (code "74") (name "unconnected-(B1B-GPIO_7-PadP9.42)") (class "Default")
      (node (ref "B1") (pin "P9.42") (pinfunction "GPIO_7_P9.42") (pintype "bidirectional"))
    )
    (net (code "75") (name "unconnected-(B1B-GPIO_14-PadP9.26)") (class "Default")
      (node (ref "B1") (pin "P9.26") (pinfunction "GPIO_14_P9.26") (pintype "bidirectional"))
    )
    (net (code "76") (name "unconnected-(B1B-GPIO_15-PadP9.24)") (class "Default")
      (node (ref "B1") (pin "P9.24") (pinfunction "GPIO_15_P9.24") (pintype "bidirectional"))
    )
    (net (code "77") (name "unconnected-(B1B-GPIO_20-PadP9.41)") (class "Default")
      (node (ref "B1") (pin "P9.41") (pinfunction "GPIO_20_P9.41") (pintype "bidirectional"))
    )
    (net (code "78") (name "unconnected-(B1B-GPIO_49-PadP9.23)") (class "Default")
      (node (ref "B1") (pin "P9.23") (pinfunction "GPIO_49_P9.23") (pintype "bidirectional"))
    )
    (net (code "79") (name "unconnected-(B1B-GPIO_60-PadP9.12)") (class "Default")
      (node (ref "B1") (pin "P9.12") (pinfunction "GPIO_60_P9.12") (pintype "bidirectional"))
    )
    (net (code "80") (name "unconnected-(B1B-GPIO_117-PadP9.25)") (class "Default")
      (node (ref "B1") (pin "P9.25") (pinfunction "GPIO_117_P9.25") (pintype "bidirectional"))
    )
    (net (code "81") (name "unconnected-(B1B-GPIO_120-PadP9.31)") (class "Default")
      (node (ref "B1") (pin "P9.31") (pinfunction "GPIO_120_P9.31") (pintype "bidirectional"))
    )
    (net (code "82") (name "unconnected-(B1B-GPIO_121-PadP9.29)") (class "Default")
      (node (ref "B1") (pin "P9.29") (pinfunction "GPIO_121_P9.29") (pintype "bidirectional"))
    )
    (net (code "83") (name "unconnected-(B1B-GPIO_122-PadP9.30)") (class "Default")
      (node (ref "B1") (pin "P9.30") (pinfunction "GPIO_122_P9.30") (pintype "bidirectional"))
    )
    (net (code "84") (name "unconnected-(B1B-GPIO_123-PadP9.28)") (class "Default")
      (node (ref "B1") (pin "P9.28") (pinfunction "GPIO_123_P9.28") (pintype "bidirectional"))
    )
    (net (code "85") (name "unconnected-(B1B-GPIO_125-PadP9.27)") (class "Default")
      (node (ref "B1") (pin "P9.27") (pinfunction "GPIO_125_P9.27") (pintype "bidirectional"))
    )
    (net (code "86") (name "unconnected-(B1B-I2C2_SCL-PadP9.19)") (class "Default")
      (node (ref "B1") (pin "P9.19") (pinfunction "I2C2_SCL_P9.19") (pintype "bidirectional"))
    )
    (net (code "87") (name "unconnected-(B1B-I2C2_SDA-PadP9.20)") (class "Default")
      (node (ref "B1") (pin "P9.20") (pinfunction "I2C2_SDA_P9.20") (pintype "bidirectional"))
    )
    (net (code "88") (name "unconnected-(B1B-SYS_5V-PadP9.7)") (class "Default")
      (node (ref "B1") (pin "P9.7") (pinfunction "SYS_5V_P9.7") (pintype "bidirectional"))
    )
    (net (code "89") (name "unconnected-(B1B-SYS_5V-PadP9.8)") (class "Default")
      (node (ref "B1") (pin "P9.8") (pinfunction "SYS_5V_P9.8") (pintype "bidirectional"))
    )
    (net (code "90") (name "unconnected-(B1B-SYS_RESET~{N}-PadP9.10)") (class "Default")
      (node (ref "B1") (pin "P9.10") (pinfunction "SYS_RESET~{N}_P9.10") (pintype "bidirectional"))
    )
    (net (code "91") (name "unconnected-(B1B-VDD_ADC-PadP9.32)") (class "Default")
      (node (ref "B1") (pin "P9.32") (pinfunction "VDD_ADC_P9.32") (pintype "bidirectional"))
    )
    (net (code "92") (name "unconnected-(U1-FB-Pad3)") (class "Default")
      (node (ref "U1") (pin "3") (pinfunction "FB_3") (pintype "bidirectional"))
    )
    (net (code "93") (name "unconnected-(U1-VOUT-Pad2)") (class "Default")
      (node (ref "U1") (pin "2") (pinfunction "VOUT_2") (pintype "bidirectional"))
    )
  )
)
